# shield_v3.net
KiCad netlist of a schematic drawn in EAGLE
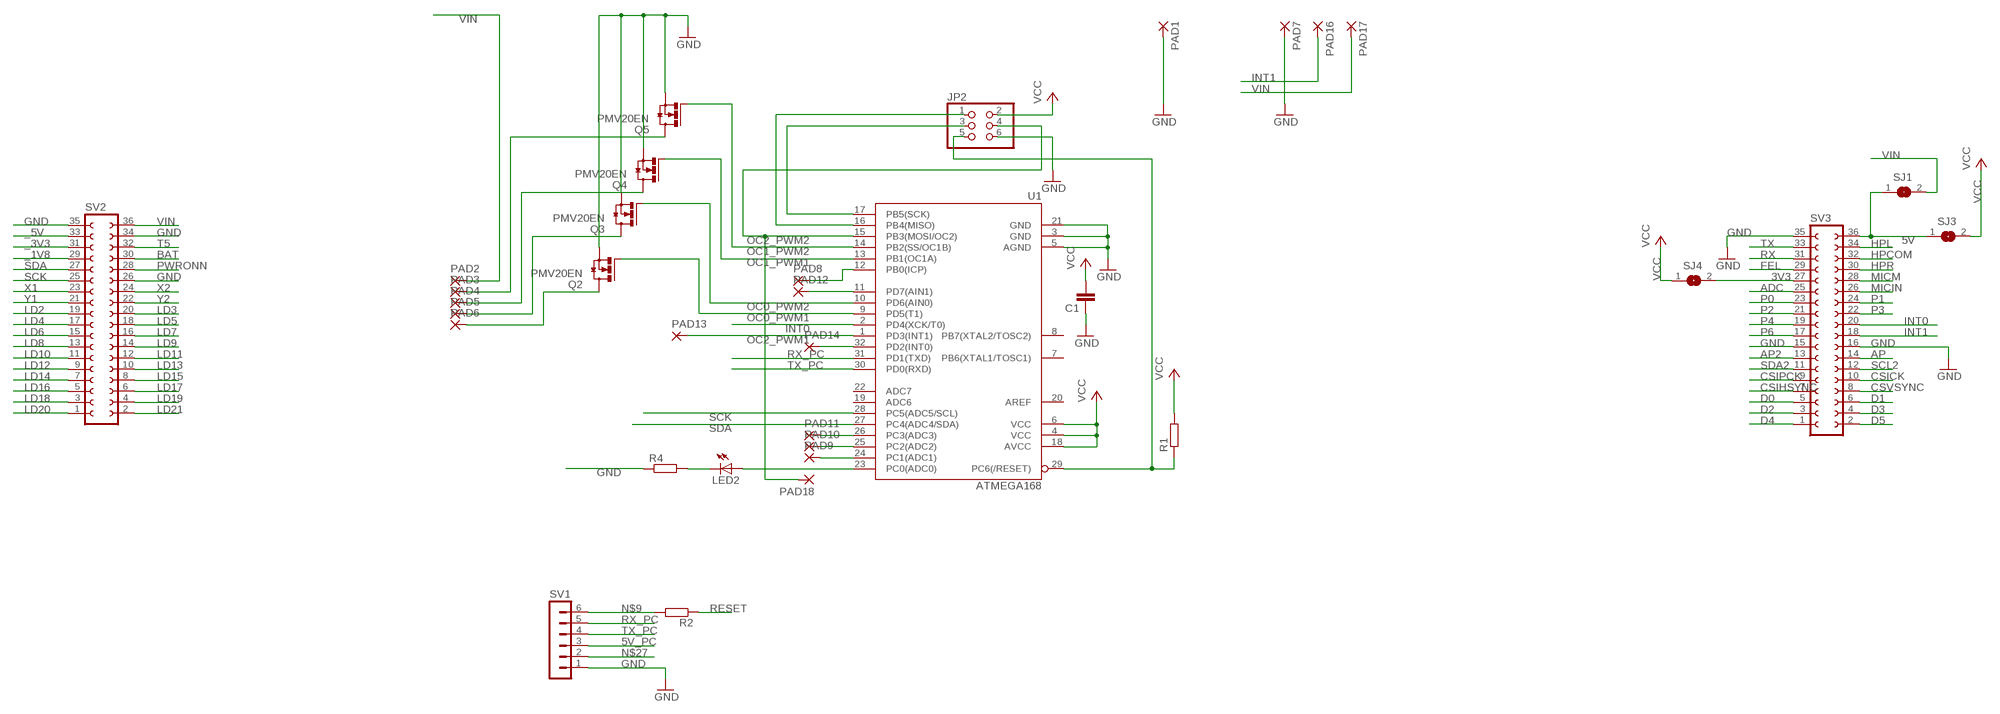
[diagram p0: schematic, sheet 1]

(export (version "E")
  (design (tool "Eeschema 10.0.6"))
  (components
    (comp (ref "C1")
      (value "C-EUC0805")
      (footprint "eagle-import:C0805")
      (libsource (lib "eagle-import") (part "C-EUC0805"))
    )
    (comp (ref "JP2")
      (value "PINHD-2X3")
      (footprint "eagle-import:2X03")
      (libsource (lib "eagle-import") (part "PINHD-2X3"))
    )
    (comp (ref "LED2")
      (value "LEDCHIP-LED0805")
      (footprint "eagle-import:CHIP-LED0805")
      (libsource (lib "eagle-import") (part "LEDCHIP-LED0805"))
    )
    (comp (ref "PAD1")
      (value "3,17/1,3")
      (footprint "eagle-import:3,17_1,3")
      (libsource (lib "eagle-import") (part "3,17/1,3"))
    )
    (comp (ref "PAD2")
      (value "3,17/1,3")
      (footprint "eagle-import:3,17_1,3")
      (libsource (lib "eagle-import") (part "3,17/1,3"))
    )
    (comp (ref "PAD3")
      (value "3,17/1,3")
      (footprint "eagle-import:3,17_1,3")
      (libsource (lib "eagle-import") (part "3,17/1,3"))
    )
    (comp (ref "PAD4")
      (value "3,17/1,3")
      (footprint "eagle-import:3,17_1,3")
      (libsource (lib "eagle-import") (part "3,17/1,3"))
    )
    (comp (ref "PAD5")
      (value "3,17/1,3")
      (footprint "eagle-import:3,17_1,3")
      (libsource (lib "eagle-import") (part "3,17/1,3"))
    )
    (comp (ref "PAD6")
      (value "3,17/1,3")
      (footprint "eagle-import:3,17_1,3")
      (libsource (lib "eagle-import") (part "3,17/1,3"))
    )
    (comp (ref "PAD7")
      (value "3,17/1,3")
      (footprint "eagle-import:3,17_1,3")
      (libsource (lib "eagle-import") (part "3,17/1,3"))
    )
    (comp (ref "PAD8")
      (value "SMD5")
      (footprint "eagle-import:SMD2,54-5,08")
      (libsource (lib "eagle-import") (part "SMD5"))
    )
    (comp (ref "PAD9")
      (value "3,17/1,3")
      (footprint "eagle-import:3,17_1,3")
      (libsource (lib "eagle-import") (part "3,17/1,3"))
    )
    (comp (ref "PAD10")
      (value "3,17/1,3")
      (footprint "eagle-import:3,17_1,3")
      (libsource (lib "eagle-import") (part "3,17/1,3"))
    )
    (comp (ref "PAD11")
      (value "3,17/1,3")
      (footprint "eagle-import:3,17_1,3")
      (libsource (lib "eagle-import") (part "3,17/1,3"))
    )
    (comp (ref "PAD12")
      (value "SMD5")
      (footprint "eagle-import:SMD2,54-5,08")
      (libsource (lib "eagle-import") (part "SMD5"))
    )
    (comp (ref "PAD13")
      (value "SMD2")
      (footprint "eagle-import:SMD1,27-2,54")
      (libsource (lib "eagle-import") (part "SMD2"))
    )
    (comp (ref "PAD14")
      (value "3,17/1,3")
      (footprint "eagle-import:3,17_1,3")
      (libsource (lib "eagle-import") (part "3,17/1,3"))
    )
    (comp (ref "PAD16")
      (value "3,17/1,3")
      (footprint "eagle-import:3,17_1,3")
      (libsource (lib "eagle-import") (part "3,17/1,3"))
    )
    (comp (ref "PAD17")
      (value "3,17/1,3")
      (footprint "eagle-import:3,17_1,3")
      (libsource (lib "eagle-import") (part "3,17/1,3"))
    )
    (comp (ref "PAD18")
      (value "3,17/1,3")
      (footprint "eagle-import:3,17_1,3")
      (libsource (lib "eagle-import") (part "3,17/1,3"))
    )
    (comp (ref "Q2")
      (value "PMV20EN")
      (footprint "eagle-import:SOT223")
      (libsource (lib "eagle-import") (part "NMOSFET_SMD_223"))
    )
    (comp (ref "Q3")
      (value "PMV20EN")
      (footprint "eagle-import:SOT223")
      (libsource (lib "eagle-import") (part "NMOSFET_SMD_223"))
    )
    (comp (ref "Q4")
      (value "PMV20EN")
      (footprint "eagle-import:SOT223")
      (libsource (lib "eagle-import") (part "NMOSFET_SMD_223"))
    )
    (comp (ref "Q5")
      (value "PMV20EN")
      (footprint "eagle-import:SOT223")
      (libsource (lib "eagle-import") (part "NMOSFET_SMD_223"))
    )
    (comp (ref "R1")
      (value "R-EU_M1206")
      (footprint "eagle-import:M1206")
      (libsource (lib "eagle-import") (part "R-EU_M1206"))
    )
    (comp (ref "R2")
      (value "R-EU_M1206")
      (footprint "eagle-import:M1206")
      (libsource (lib "eagle-import") (part "R-EU_M1206"))
    )
    (comp (ref "R4")
      (value "R-EU_M1206")
      (footprint "eagle-import:M1206")
      (libsource (lib "eagle-import") (part "R-EU_M1206"))
    )
    (comp (ref "SJ1") (value "SJ") (footprint "eagle-import:SJ") (libsource (lib "eagle-import") (part "SJ")))
    (comp (ref "SJ3") (value "SJ") (footprint "eagle-import:SJ") (libsource (lib "eagle-import") (part "SJ")))
    (comp (ref "SJ4") (value "SJ") (footprint "eagle-import:SJ") (libsource (lib "eagle-import") (part "SJ")))
    (comp (ref "SV1")
      (value "MA06-1")
      (footprint "eagle-import:MA06-1")
      (libsource (lib "eagle-import") (part "MA06-1"))
    )
    (comp (ref "SV2")
      (value "FE18-2")
      (footprint "eagle-import:FE18-2")
      (libsource (lib "eagle-import") (part "FE18-2"))
    )
    (comp (ref "SV3")
      (value "FE18-2")
      (footprint "eagle-import:FE18-2")
      (libsource (lib "eagle-import") (part "FE18-2"))
    )
    (comp (ref "U1")
      (value "ATMEGA168")
      (footprint "eagle-import:TQFP32-08")
      (libsource (lib "eagle-import") (part "ATMEGA168"))
    )
  )
  (nets
    (net (code "1") (name "/3V3") (class "Default")
      (node (ref "SJ4") (pin "2") (pinfunction "2_2") (pintype "passive"))
      (node (ref "SV3") (pin "27") (pinfunction "27_27") (pintype "passive"))
    )
    (net (code "2") (name "/5V") (class "Default")
      (node (ref "SJ1") (pin "1") (pinfunction "1_1") (pintype "passive"))
      (node (ref "SJ3") (pin "1") (pinfunction "1_1") (pintype "passive"))
      (node (ref "SV3") (pin "36") (pinfunction "36_36") (pintype "passive"))
    )
    (net (code "3") (name "/5V_PC") (class "Default")
      (node (ref "SV1") (pin "3") (pinfunction "3_3") (pintype "passive"))
    )
    (net (code "4") (name "/ADC") (class "Default")
      (node (ref "SV3") (pin "25") (pinfunction "25_25") (pintype "passive"))
    )
    (net (code "5") (name "/AP") (class "Default")
      (node (ref "SV3") (pin "14") (pinfunction "14_14") (pintype "passive"))
    )
    (net (code "6") (name "/AP2") (class "Default")
      (node (ref "SV3") (pin "13") (pinfunction "13_13") (pintype "passive"))
    )
    (net (code "7") (name "/BAT") (class "Default")
      (node (ref "SV2") (pin "30") (pinfunction "30_30") (pintype "passive"))
    )
    (net (code "8") (name "/CSICK") (class "Default")
      (node (ref "SV3") (pin "10") (pinfunction "10_10") (pintype "passive"))
    )
    (net (code "9") (name "/CSIHSYNC") (class "Default")
      (node (ref "SV3") (pin "7") (pinfunction "7_7") (pintype "passive"))
    )
    (net (code "10") (name "/CSIPCK") (class "Default")
      (node (ref "SV3") (pin "9") (pinfunction "9_9") (pintype "passive"))
    )
    (net (code "11") (name "/CSVSYNC") (class "Default")
      (node (ref "SV3") (pin "8") (pinfunction "8_8") (pintype "passive"))
    )
    (net (code "12") (name "/D0") (class "Default")
      (node (ref "SV3") (pin "5") (pinfunction "5_5") (pintype "passive"))
    )
    (net (code "13") (name "/D1") (class "Default")
      (node (ref "SV3") (pin "6") (pinfunction "6_6") (pintype "passive"))
    )
    (net (code "14") (name "/D2") (class "Default")
      (node (ref "SV3") (pin "3") (pinfunction "3_3") (pintype "passive"))
    )
    (net (code "15") (name "/D3") (class "Default")
      (node (ref "SV3") (pin "4") (pinfunction "4_4") (pintype "passive"))
    )
    (net (code "16") (name "/D4") (class "Default")
      (node (ref "SV3") (pin "1") (pinfunction "1_1") (pintype "passive"))
    )
    (net (code "17") (name "/D5") (class "Default")
      (node (ref "SV3") (pin "2") (pinfunction "2_2") (pintype "passive"))
    )
    (net (code "18") (name "/FEL") (class "Default")
      (node (ref "SV3") (pin "29") (pinfunction "29_29") (pintype "passive"))
    )
    (net (code "19") (name "/HPCOM") (class "Default")
      (node (ref "SV3") (pin "32") (pinfunction "32_32") (pintype "passive"))
    )
    (net (code "20") (name "/HPL") (class "Default")
      (node (ref "SV3") (pin "34") (pinfunction "34_34") (pintype "passive"))
    )
    (net (code "21") (name "/HPR") (class "Default")
      (node (ref "SV3") (pin "30") (pinfunction "30_30") (pintype "passive"))
    )
    (net (code "22") (name "/INT0") (class "Default")
      (node (ref "SV3") (pin "20") (pinfunction "20_20") (pintype "passive"))
      (node (ref "U1") (pin "2") (pinfunction "PD4(XCK/T0)_2") (pintype "bidirectional"))
    )
    (net (code "23") (name "/INT1") (class "Default")
      (node (ref "PAD16") (pin "1") (pinfunction "P_1") (pintype "passive"))
      (node (ref "SV3") (pin "18") (pinfunction "18_18") (pintype "passive"))
    )
    (net (code "24") (name "/LD2") (class "Default")
      (node (ref "SV2") (pin "19") (pinfunction "19_19") (pintype "passive"))
    )
    (net (code "25") (name "/LD3") (class "Default")
      (node (ref "SV2") (pin "20") (pinfunction "20_20") (pintype "passive"))
    )
    (net (code "26") (name "/LD4") (class "Default")
      (node (ref "SV2") (pin "17") (pinfunction "17_17") (pintype "passive"))
    )
    (net (code "27") (name "/LD5") (class "Default")
      (node (ref "SV2") (pin "18") (pinfunction "18_18") (pintype "passive"))
    )
    (net (code "28") (name "/LD6") (class "Default")
      (node (ref "SV2") (pin "15") (pinfunction "15_15") (pintype "passive"))
    )
    (net (code "29") (name "/LD7") (class "Default")
      (node (ref "SV2") (pin "16") (pinfunction "16_16") (pintype "passive"))
    )
    (net (code "30") (name "/LD8") (class "Default")
      (node (ref "SV2") (pin "13") (pinfunction "13_13") (pintype "passive"))
    )
    (net (code "31") (name "/LD9") (class "Default")
      (node (ref "SV2") (pin "14") (pinfunction "14_14") (pintype "passive"))
    )
    (net (code "32") (name "/LD10") (class "Default")
      (node (ref "SV2") (pin "11") (pinfunction "11_11") (pintype "passive"))
    )
    (net (code "33") (name "/LD11") (class "Default")
      (node (ref "SV2") (pin "12") (pinfunction "12_12") (pintype "passive"))
    )
    (net (code "34") (name "/LD12") (class "Default")
      (node (ref "SV2") (pin "9") (pinfunction "9_9") (pintype "passive"))
    )
    (net (code "35") (name "/LD13") (class "Default")
      (node (ref "SV2") (pin "10") (pinfunction "10_10") (pintype "passive"))
    )
    (net (code "36") (name "/LD14") (class "Default")
      (node (ref "SV2") (pin "7") (pinfunction "7_7") (pintype "passive"))
    )
    (net (code "37") (name "/LD15") (class "Default")
      (node (ref "SV2") (pin "8") (pinfunction "8_8") (pintype "passive"))
    )
    (net (code "38") (name "/LD16") (class "Default")
      (node (ref "SV2") (pin "5") (pinfunction "5_5") (pintype "passive"))
    )
    (net (code "39") (name "/LD17") (class "Default")
      (node (ref "SV2") (pin "6") (pinfunction "6_6") (pintype "passive"))
    )
    (net (code "40") (name "/LD18") (class "Default")
      (node (ref "SV2") (pin "3") (pinfunction "3_3") (pintype "passive"))
    )
    (net (code "41") (name "/LD19") (class "Default")
      (node (ref "SV2") (pin "4") (pinfunction "4_4") (pintype "passive"))
    )
    (net (code "42") (name "/LD20") (class "Default")
      (node (ref "SV2") (pin "1") (pinfunction "1_1") (pintype "passive"))
    )
    (net (code "43") (name "/LD21") (class "Default")
      (node (ref "SV2") (pin "2") (pinfunction "2_2") (pintype "passive"))
    )
    (net (code "44") (name "/MICIN") (class "Default")
      (node (ref "SV3") (pin "26") (pinfunction "26_26") (pintype "passive"))
    )
    (net (code "45") (name "/MICM") (class "Default")
      (node (ref "SV3") (pin "28") (pinfunction "28_28") (pintype "passive"))
    )
    (net (code "46") (name "/N$9") (class "Default")
      (node (ref "R2") (pin "2") (pinfunction "2_2") (pintype "passive"))
      (node (ref "SV1") (pin "6") (pinfunction "6_6") (pintype "passive"))
    )
    (net (code "47") (name "/N$27") (class "Default")
      (node (ref "SV1") (pin "2") (pinfunction "2_2") (pintype "passive"))
    )
    (net (code "48") (name "/OC0_PWM1") (class "Default")
      (node (ref "Q2") (pin "1") (pinfunction "G_1") (pintype "passive"))
      (node (ref "U1") (pin "9") (pinfunction "PD5(T1)_9") (pintype "bidirectional"))
    )
    (net (code "49") (name "/OC0_PWM2") (class "Default")
      (node (ref "Q3") (pin "1") (pinfunction "G_1") (pintype "passive"))
      (node (ref "U1") (pin "10") (pinfunction "PD6(AIN0)_10") (pintype "bidirectional"))
    )
    (net (code "50") (name "/OC1_PWM1") (class "Default")
      (node (ref "Q4") (pin "1") (pinfunction "G_1") (pintype "passive"))
      (node (ref "U1") (pin "13") (pinfunction "PB1(OC1A)_13") (pintype "bidirectional"))
    )
    (net (code "51") (name "/OC1_PWM2") (class "Default")
      (node (ref "Q5") (pin "1") (pinfunction "G_1") (pintype "passive"))
      (node (ref "U1") (pin "14") (pinfunction "PB2(SS/OC1B)_14") (pintype "bidirectional"))
    )
    (net (code "52") (name "/OC2_PWM1") (class "Default")
      (node (ref "PAD13") (pin "1") (pinfunction "P_1") (pintype "passive"))
      (node (ref "U1") (pin "1") (pinfunction "PD3(INT1)_1") (pintype "bidirectional"))
    )
    (net (code "53") (name "/OC2_PWM2") (class "Default")
      (node (ref "JP2") (pin "4") (pinfunction "4_4") (pintype "passive"))
      (node (ref "PAD18") (pin "1") (pinfunction "P_1") (pintype "passive"))
      (node (ref "U1") (pin "15") (pinfunction "PB3(MOSI/OC2)_15") (pintype "bidirectional"))
    )
    (net (code "54") (name "/P0") (class "Default")
      (node (ref "SV3") (pin "23") (pinfunction "23_23") (pintype "passive"))
    )
    (net (code "55") (name "/P1") (class "Default")
      (node (ref "SV3") (pin "24") (pinfunction "24_24") (pintype "passive"))
    )
    (net (code "56") (name "/P2") (class "Default")
      (node (ref "SV3") (pin "21") (pinfunction "21_21") (pintype "passive"))
    )
    (net (code "57") (name "/P3") (class "Default")
      (node (ref "SV3") (pin "22") (pinfunction "22_22") (pintype "passive"))
    )
    (net (code "58") (name "/P4") (class "Default")
      (node (ref "SV3") (pin "19") (pinfunction "19_19") (pintype "passive"))
    )
    (net (code "59") (name "/P6") (class "Default")
      (node (ref "SV3") (pin "17") (pinfunction "17_17") (pintype "passive"))
    )
    (net (code "60") (name "/PWRONN") (class "Default")
      (node (ref "SV2") (pin "28") (pinfunction "28_28") (pintype "passive"))
    )
    (net (code "61") (name "/RESET") (class "Default")
      (node (ref "JP2") (pin "5") (pinfunction "5_5") (pintype "passive"))
      (node (ref "R1") (pin "1") (pinfunction "1_1") (pintype "passive"))
      (node (ref "R2") (pin "1") (pinfunction "1_1") (pintype "passive"))
      (node (ref "U1") (pin "29") (pinfunction "PC6(/RESET)_29") (pintype "bidirectional"))
    )
    (net (code "62") (name "/RX") (class "Default")
      (node (ref "SV3") (pin "31") (pinfunction "31_31") (pintype "passive"))
    )
    (net (code "63") (name "/RX_PC") (class "Default")
      (node (ref "SV1") (pin "5") (pinfunction "5_5") (pintype "passive"))
      (node (ref "U1") (pin "31") (pinfunction "PD1(TXD)_31") (pintype "bidirectional"))
    )
    (net (code "64") (name "/SCK") (class "Default")
      (node (ref "SV2") (pin "25") (pinfunction "25_25") (pintype "passive"))
      (node (ref "U1") (pin "28") (pinfunction "PC5(ADC5/SCL)_28") (pintype "bidirectional"))
    )
    (net (code "65") (name "/SCL2") (class "Default")
      (node (ref "SV3") (pin "12") (pinfunction "12_12") (pintype "passive"))
    )
    (net (code "66") (name "/SDA") (class "Default")
      (node (ref "SV2") (pin "27") (pinfunction "27_27") (pintype "passive"))
      (node (ref "U1") (pin "27") (pinfunction "PC4(ADC4/SDA)_27") (pintype "bidirectional"))
    )
    (net (code "67") (name "/SDA2") (class "Default")
      (node (ref "SV3") (pin "11") (pinfunction "11_11") (pintype "passive"))
    )
    (net (code "68") (name "/T5") (class "Default")
      (node (ref "SV2") (pin "32") (pinfunction "32_32") (pintype "passive"))
    )
    (net (code "69") (name "/TX") (class "Default")
      (node (ref "SV3") (pin "33") (pinfunction "33_33") (pintype "passive"))
    )
    (net (code "70") (name "/TX_PC") (class "Default")
      (node (ref "SV1") (pin "4") (pinfunction "4_4") (pintype "passive"))
      (node (ref "U1") (pin "30") (pinfunction "PD0(RXD)_30") (pintype "bidirectional"))
    )
    (net (code "71") (name "/VIN") (class "Default")
      (node (ref "PAD17") (pin "1") (pinfunction "P_1") (pintype "passive"))
      (node (ref "PAD2") (pin "1") (pinfunction "P_1") (pintype "passive"))
      (node (ref "SJ1") (pin "2") (pinfunction "2_2") (pintype "passive"))
      (node (ref "SV2") (pin "36") (pinfunction "36_36") (pintype "passive"))
    )
    (net (code "72") (name "/X1") (class "Default")
      (node (ref "SV2") (pin "23") (pinfunction "23_23") (pintype "passive"))
    )
    (net (code "73") (name "/X2") (class "Default")
      (node (ref "SV2") (pin "24") (pinfunction "24_24") (pintype "passive"))
    )
    (net (code "74") (name "/Y1") (class "Default")
      (node (ref "SV2") (pin "21") (pinfunction "21_21") (pintype "passive"))
    )
    (net (code "75") (name "/Y2") (class "Default")
      (node (ref "SV2") (pin "22") (pinfunction "22_22") (pintype "passive"))
    )
    (net (code "76") (name "/_1V8") (class "Default")
      (node (ref "SV2") (pin "29") (pinfunction "29_29") (pintype "passive"))
    )
    (net (code "77") (name "/_3V3") (class "Default")
      (node (ref "SV2") (pin "31") (pinfunction "31_31") (pintype "passive"))
    )
    (net (code "78") (name "/_5V") (class "Default")
      (node (ref "SV2") (pin "33") (pinfunction "33_33") (pintype "passive"))
    )
    (net (code "79") (name "GND") (class "Default")
      (node (ref "C1") (pin "1") (pinfunction "1_1") (pintype "passive"))
      (node (ref "JP2") (pin "6") (pinfunction "6_6") (pintype "passive"))
      (node (ref "PAD1") (pin "1") (pinfunction "P_1") (pintype "passive"))
      (node (ref "PAD7") (pin "1") (pinfunction "P_1") (pintype "passive"))
      (node (ref "Q2") (pin "3") (pinfunction "S_3") (pintype "passive"))
      (node (ref "Q3") (pin "3") (pinfunction "S_3") (pintype "passive"))
      (node (ref "Q4") (pin "3") (pinfunction "S_3") (pintype "passive"))
      (node (ref "Q5") (pin "3") (pinfunction "S_3") (pintype "passive"))
      (node (ref "R4") (pin "1") (pinfunction "1_1") (pintype "passive"))
      (node (ref "SV1") (pin "1") (pinfunction "1_1") (pintype "passive"))
      (node (ref "SV2") (pin "26") (pinfunction "26_26") (pintype "passive"))
      (node (ref "SV2") (pin "34") (pinfunction "34_34") (pintype "passive"))
      (node (ref "SV2") (pin "35") (pinfunction "35_35") (pintype "passive"))
      (node (ref "SV3") (pin "15") (pinfunction "15_15") (pintype "passive"))
      (node (ref "SV3") (pin "16") (pinfunction "16_16") (pintype "passive"))
      (node (ref "SV3") (pin "35") (pinfunction "35_35") (pintype "passive"))
      (node (ref "U1") (pin "21") (pinfunction "GND_21") (pintype "bidirectional"))
      (node (ref "U1") (pin "3") (pinfunction "GND_3") (pintype "bidirectional"))
      (node (ref "U1") (pin "5") (pinfunction "AGND_5") (pintype "bidirectional"))
    )
    (net (code "80") (name "Net-(LED2-PadC)") (class "Default")
      (node (ref "LED2") (pin "C") (pinfunction "C_C") (pintype "passive"))
      (node (ref "R4") (pin "2") (pinfunction "2_2") (pintype "passive"))
    )
    (net (code "81") (name "Net-(PAD3-P)") (class "Default")
      (node (ref "PAD3") (pin "1") (pinfunction "P_1") (pintype "passive"))
      (node (ref "Q5") (pin "2") (pinfunction "D_2") (pintype "passive"))
      (node (ref "Q5") (pin "4") (pinfunction "D_4") (pintype "passive"))
    )
    (net (code "82") (name "Net-(PAD4-P)") (class "Default")
      (node (ref "PAD4") (pin "1") (pinfunction "P_1") (pintype "passive"))
      (node (ref "Q4") (pin "2") (pinfunction "D_2") (pintype "passive"))
      (node (ref "Q4") (pin "4") (pinfunction "D_4") (pintype "passive"))
    )
    (net (code "83") (name "Net-(PAD5-P)") (class "Default")
      (node (ref "PAD5") (pin "1") (pinfunction "P_1") (pintype "passive"))
      (node (ref "Q3") (pin "2") (pinfunction "D_2") (pintype "passive"))
      (node (ref "Q3") (pin "4") (pinfunction "D_4") (pintype "passive"))
    )
    (net (code "84") (name "Net-(PAD6-P)") (class "Default")
      (node (ref "PAD6") (pin "1") (pinfunction "P_1") (pintype "passive"))
      (node (ref "Q2") (pin "2") (pinfunction "D_2") (pintype "passive"))
      (node (ref "Q2") (pin "4") (pinfunction "D_4") (pintype "passive"))
    )
    (net (code "85") (name "Net-(PAD8-P)") (class "Default")
      (node (ref "PAD8") (pin "1") (pinfunction "P_1") (pintype "passive"))
      (node (ref "U1") (pin "12") (pinfunction "PB0(ICP)_12") (pintype "bidirectional"))
    )
    (net (code "86") (name "Net-(PAD9-P)") (class "Default")
      (node (ref "PAD9") (pin "1") (pinfunction "P_1") (pintype "passive"))
      (node (ref "U1") (pin "24") (pinfunction "PC1(ADC1)_24") (pintype "bidirectional"))
    )
    (net (code "87") (name "Net-(PAD10-P)") (class "Default")
      (node (ref "PAD10") (pin "1") (pinfunction "P_1") (pintype "passive"))
      (node (ref "U1") (pin "25") (pinfunction "PC2(ADC2)_25") (pintype "bidirectional"))
    )
    (net (code "88") (name "Net-(PAD11-P)") (class "Default")
      (node (ref "PAD11") (pin "1") (pinfunction "P_1") (pintype "passive"))
      (node (ref "U1") (pin "26") (pinfunction "PC3(ADC3)_26") (pintype "bidirectional"))
    )
    (net (code "89") (name "Net-(PAD12-P)") (class "Default")
      (node (ref "PAD12") (pin "1") (pinfunction "P_1") (pintype "passive"))
      (node (ref "U1") (pin "11") (pinfunction "PD7(AIN1)_11") (pintype "bidirectional"))
    )
    (net (code "90") (name "Net-(PAD14-P)") (class "Default")
      (node (ref "PAD14") (pin "1") (pinfunction "P_1") (pintype "passive"))
      (node (ref "U1") (pin "32") (pinfunction "PD2(INT0)_32") (pintype "bidirectional"))
    )
    (net (code "91") (name "Net-(U1-PB4(MISO))") (class "Default")
      (node (ref "JP2") (pin "1") (pinfunction "1_1") (pintype "passive"))
      (node (ref "U1") (pin "16") (pinfunction "PB4(MISO)_16") (pintype "bidirectional"))
    )
    (net (code "92") (name "Net-(U1-PB5(SCK))") (class "Default")
      (node (ref "JP2") (pin "3") (pinfunction "3_3") (pintype "passive"))
      (node (ref "U1") (pin "17") (pinfunction "PB5(SCK)_17") (pintype "bidirectional"))
    )
    (net (code "93") (name "Net-(U1-PC0(ADC0))") (class "Default")
      (node (ref "LED2") (pin "A") (pinfunction "A_A") (pintype "passive"))
      (node (ref "U1") (pin "23") (pinfunction "PC0(ADC0)_23") (pintype "bidirectional"))
    )
    (net (code "94") (name "VCC") (class "Default")
      (node (ref "C1") (pin "2") (pinfunction "2_2") (pintype "passive"))
      (node (ref "JP2") (pin "2") (pinfunction "2_2") (pintype "passive"))
      (node (ref "R1") (pin "2") (pinfunction "2_2") (pintype "passive"))
      (node (ref "SJ3") (pin "2") (pinfunction "2_2") (pintype "passive"))
      (node (ref "SJ4") (pin "1") (pinfunction "1_1") (pintype "passive"))
      (node (ref "U1") (pin "18") (pinfunction "AVCC_18") (pintype "bidirectional"))
      (node (ref "U1") (pin "4") (pinfunction "VCC_4") (pintype "bidirectional"))
      (node (ref "U1") (pin "6") (pinfunction "VCC_6") (pintype "bidirectional"))
    )
    (net (code "95") (name "unconnected-(U1-ADC6-Pad19)") (class "Default")
      (node (ref "U1") (pin "19") (pinfunction "ADC6_19") (pintype "bidirectional"))
    )
    (net (code "96") (name "unconnected-(U1-ADC7-Pad22)") (class "Default")
      (node (ref "U1") (pin "22") (pinfunction "ADC7_22") (pintype "bidirectional"))
    )
    (net (code "97") (name "unconnected-(U1-AREF-Pad20)") (class "Default")
      (node (ref "U1") (pin "20") (pinfunction "AREF_20") (pintype "bidirectional"))
    )
    (net (code "98") (name "unconnected-(U1-PB6(XTAL1{slash}TOSC1)-Pad7)") (class "Default")
      (node (ref "U1") (pin "7") (pinfunction "PB6(XTAL1/TOSC1)_7") (pintype "bidirectional"))
    )
    (net (code "99") (name "unconnected-(U1-PB7(XTAL2{slash}TOSC2)-Pad8)") (class "Default")
      (node (ref "U1") (pin "8") (pinfunction "PB7(XTAL2/TOSC2)_8") (pintype "bidirectional"))
    )
  )
)
